# ZYNQ_PW.net
KiCad netlist of a schematic drawn in Altium Designer
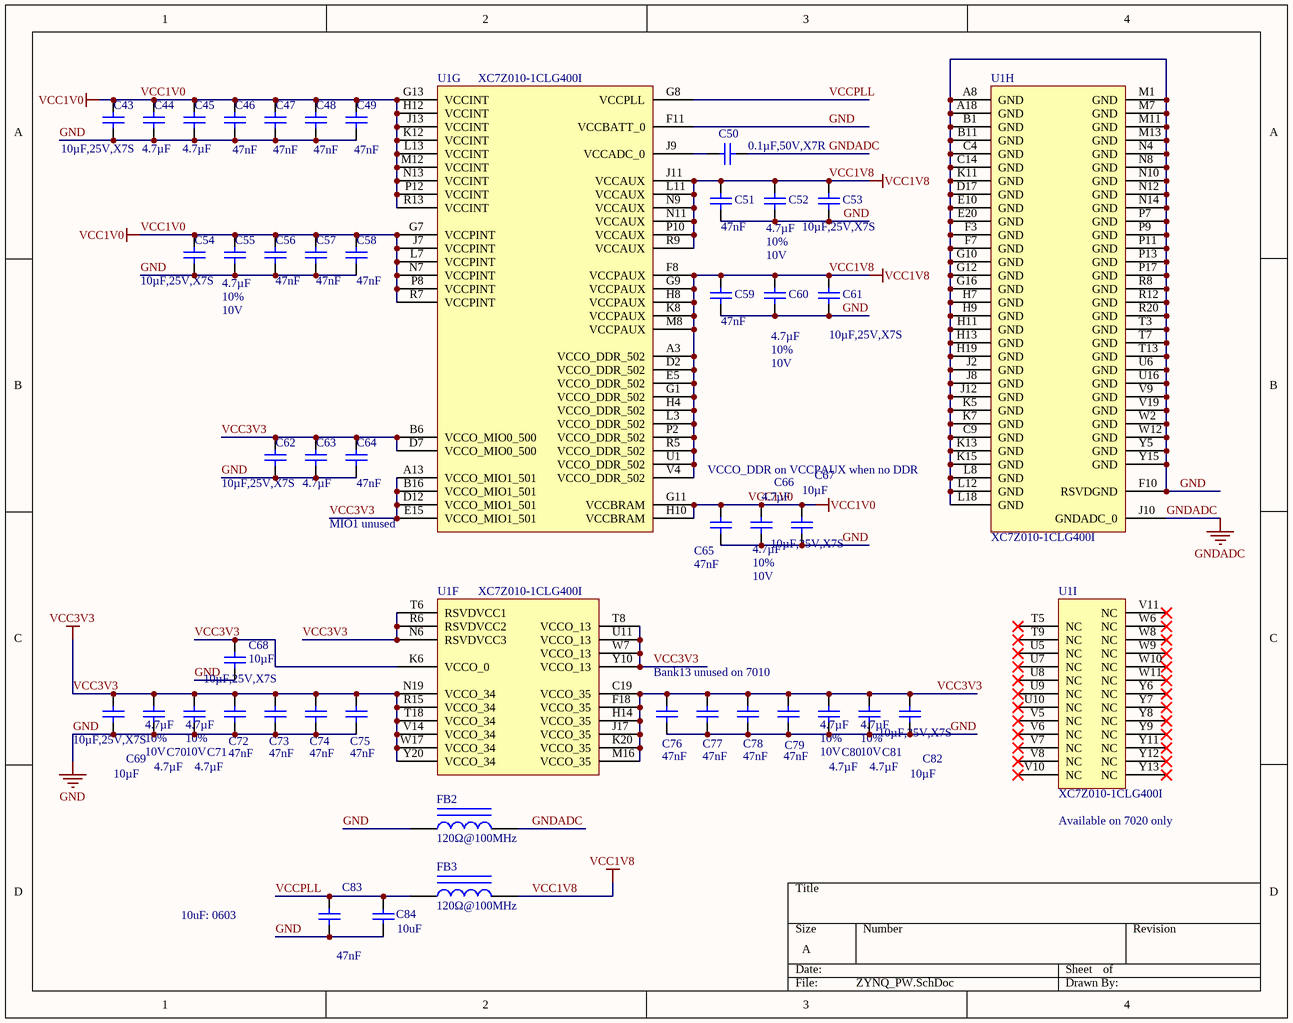
[diagram p0: ZYNQ_PW.SchDoc]

(export (version "E")
  (design (tool "Eeschema 10.0.6"))
  (components
    (comp (ref "C43")
      (value "10µF,25V,X7S")
      (footprint "CAP0805i")
      (description "0805, 10uF, 10%, 25V, X7S")
      (fields (field (name "PART NUMBER") "GRT21BC71E106KE13L") (field (name "VOLTAGE") "25V"))
      (libsource (lib "AmpherLib") (part "Cap_10uF_50V_X7S_0805"))
    )
    (comp (ref "C44")
      (value "4.7µF")
      (footprint "CAP0402i")
      (description "CAP CER 4.7UF 10V X5R 0402")
      (fields (field (name "PART NUMBER") "C1005X5R1A475K050BC") (field (name "TOLERANCE") "10%"))
      (libsource (lib "AmpherLib") (part "Cap_4.7uF_10V_10%_0402"))
    )
    (comp (ref "C45")
      (value "4.7µF")
      (footprint "CAP0402i")
      (description "CAP CER 4.7UF 10V X5R 0402")
      (fields
        (field (name "PART NUMBER") "C1005X5R1A475K050BC")
        (field (name "CAPACITANCE") "4.7µF")
        (field (name "TOLERANCE") "10%")
      )
      (libsource (lib "AmpherLib") (part "Cap_4.7uF_10V_10%_0402"))
    )
    (comp (ref "C46")
      (value "~")
      (footprint "CAP0201i")
      (description "0201, 47nF, 10%, 25V, X7R")
      (fields (field (name "CAPACITANCE") "47nF"))
      (libsource (lib "AmpherLib") (part "Cap_47nF_X7R_0201"))
    )
    (comp (ref "C47")
      (value "~")
      (footprint "CAP0201i")
      (description "0201, 47nF, 10%, 25V, X7R")
      (fields (field (name "CAPACITANCE") "47nF"))
      (libsource (lib "AmpherLib") (part "Cap_47nF_X7R_0201"))
    )
    (comp (ref "C48")
      (value "~")
      (footprint "CAP0201i")
      (description "0201, 47nF, 10%, 25V, X7R")
      (fields (field (name "CAPACITANCE") "47nF"))
      (libsource (lib "AmpherLib") (part "Cap_47nF_X7R_0201"))
    )
    (comp (ref "C49")
      (value "~")
      (footprint "CAP0201i")
      (description "0201, 47nF, 10%, 25V, X7R")
      (fields (field (name "CAPACITANCE") "47nF"))
      (libsource (lib "AmpherLib") (part "Cap_47nF_X7R_0201"))
    )
    (comp (ref "C50")
      (value "0.1µF,50V,X7R")
      (footprint "CAP0402i")
      (description "0402, 0.1uF, 10%,  50V, X7R")
      (fields (field (name "PART NUMBER") "C1005X7R1H104K050BE") (field (name "VOLTAGE") "50V"))
      (libsource (lib "AmpherLib") (part "Cap_0.1uF_50V_X7R_0402"))
    )
    (comp (ref "C51")
      (value "~")
      (footprint "CAP0201i")
      (description "0201, 47nF, 10%, 25V, X7R")
      (fields (field (name "CAPACITANCE") "47nF"))
      (libsource (lib "AmpherLib") (part "Cap_47nF_X7R_0201"))
    )
    (comp (ref "C52")
      (value "4.7µF")
      (footprint "CAP0402i")
      (description "CAP CER 4.7UF 10V X5R 0402")
      (fields
        (field (name "PART NUMBER") "C1005X5R1A475K050BC")
        (field (name "CAPACITANCE") "4.7µF")
        (field (name "TOLERANCE") "10%")
        (field (name "VOLTAGE RATING") "10V")
      )
      (libsource (lib "AmpherLib") (part "Cap_4.7uF_10V_10%_0402"))
    )
    (comp (ref "C53")
      (value "10µF,25V,X7S")
      (footprint "CAP0805i")
      (description "0805, 10uF, 10%, 25V, X7S")
      (fields (field (name "PART NUMBER") "GRT21BC71E106KE13L") (field (name "VOLTAGE") "25V"))
      (libsource (lib "AmpherLib") (part "Cap_10uF_50V_X7S_0805"))
    )
    (comp (ref "C54")
      (value "10µF,25V,X7S")
      (footprint "CAP0805i")
      (description "0805, 10uF, 10%, 25V, X7S")
      (fields (field (name "PART NUMBER") "GRT21BC71E106KE13L") (field (name "VOLTAGE") "25V"))
      (libsource (lib "AmpherLib") (part "Cap_10uF_50V_X7S_0805"))
    )
    (comp (ref "C55")
      (value "4.7µF")
      (footprint "CAP0402i")
      (description "CAP CER 4.7UF 10V X5R 0402")
      (fields
        (field (name "PART NUMBER") "C1005X5R1A475K050BC")
        (field (name "CAPACITANCE") "4.7µF")
        (field (name "TOLERANCE") "10%")
        (field (name "VOLTAGE RATING") "10V")
      )
      (libsource (lib "AmpherLib") (part "Cap_4.7uF_10V_10%_0402"))
    )
    (comp (ref "C56")
      (value "~")
      (footprint "CAP0201i")
      (description "0201, 47nF, 10%, 25V, X7R")
      (fields (field (name "CAPACITANCE") "47nF"))
      (libsource (lib "AmpherLib") (part "Cap_47nF_X7R_0201"))
    )
    (comp (ref "C57")
      (value "~")
      (footprint "CAP0201i")
      (description "0201, 47nF, 10%, 25V, X7R")
      (fields (field (name "CAPACITANCE") "47nF"))
      (libsource (lib "AmpherLib") (part "Cap_47nF_X7R_0201"))
    )
    (comp (ref "C58")
      (value "~")
      (footprint "CAP0201i")
      (description "0201, 47nF, 10%, 25V, X7R")
      (fields (field (name "CAPACITANCE") "47nF"))
      (libsource (lib "AmpherLib") (part "Cap_47nF_X7R_0201"))
    )
    (comp (ref "C59")
      (value "~")
      (footprint "CAP0201i")
      (description "0201, 47nF, 10%, 25V, X7R")
      (fields (field (name "CAPACITANCE") "47nF"))
      (libsource (lib "AmpherLib") (part "Cap_47nF_X7R_0201"))
    )
    (comp (ref "C60")
      (value "4.7µF")
      (footprint "CAP0402i")
      (description "CAP CER 4.7UF 10V X5R 0402")
      (fields
        (field (name "PART NUMBER") "C1005X5R1A475K050BC")
        (field (name "CAPACITANCE") "4.7µF")
        (field (name "TOLERANCE") "10%")
        (field (name "VOLTAGE RATING") "10V")
      )
      (libsource (lib "AmpherLib") (part "Cap_4.7uF_10V_10%_0402"))
    )
    (comp (ref "C61")
      (value "10µF,25V,X7S")
      (footprint "CAP0805i")
      (description "0805, 10uF, 10%, 25V, X7S")
      (fields (field (name "PART NUMBER") "GRT21BC71E106KE13L") (field (name "VOLTAGE") "25V"))
      (libsource (lib "AmpherLib") (part "Cap_10uF_50V_X7S_0805"))
    )
    (comp (ref "C62")
      (value "10µF,25V,X7S")
      (footprint "CAP0805i")
      (description "0805, 10uF, 10%, 25V, X7S")
      (fields (field (name "PART NUMBER") "GRT21BC71E106KE13L") (field (name "VOLTAGE") "25V"))
      (libsource (lib "AmpherLib") (part "Cap_10uF_50V_X7S_0805"))
    )
    (comp (ref "C63")
      (value "4.7µF")
      (footprint "CAP0402i")
      (description "CAP CER 4.7UF 10V X5R 0402")
      (fields (field (name "PART NUMBER") "C1005X5R1A475K050BC") (field (name "TOLERANCE") "10%"))
      (libsource (lib "AmpherLib") (part "Cap_4.7uF_10V_10%_0402"))
    )
    (comp (ref "C64")
      (value "~")
      (footprint "CAP0201i")
      (description "0201, 47nF, 10%, 25V, X7R")
      (fields (field (name "CAPACITANCE") "47nF"))
      (libsource (lib "AmpherLib") (part "Cap_47nF_X7R_0201"))
    )
    (comp (ref "C65")
      (value "~")
      (footprint "CAP0201i")
      (description "0201, 47nF, 10%, 25V, X7R")
      (fields (field (name "CAPACITANCE") "47nF"))
      (libsource (lib "AmpherLib") (part "Cap_47nF_X7R_0201"))
    )
    (comp (ref "C66")
      (value "4.7µF")
      (footprint "CAP0402i")
      (description "CAP CER 4.7UF 10V X5R 0402")
      (fields
        (field (name "PART NUMBER") "C1005X5R1A475K050BC")
        (field (name "CAPACITANCE") "4.7µF")
        (field (name "TOLERANCE") "10%")
        (field (name "VOLTAGE RATING") "10V")
      )
      (libsource (lib "AmpherLib") (part "Cap_4.7uF_10V_10%_0402"))
    )
    (comp (ref "C67")
      (value "10µF")
      (footprint "CAP0805i")
      (description "0805, 10uF, 10%, 25V, X7S")
      (fields
        (field (name "PART NUMBER") "GRT21BC71E106KE13L")
        (field (name "VOLTAGE") "25V")
        (field (name "ALTIUM_VALUE") "10µF,25V,X7S")
      )
      (libsource (lib "AmpherLib") (part "Cap_10uF_50V_X7S_0805"))
    )
    (comp (ref "C68")
      (value "10µF")
      (footprint "CAP0805i")
      (description "0805, 10uF, 10%, 25V, X7S")
      (fields
        (field (name "PART NUMBER") "GRT21BC71E106KE13L")
        (field (name "VOLTAGE") "25V")
        (field (name "ALTIUM_VALUE") "10µF,25V,X7S")
      )
      (libsource (lib "AmpherLib") (part "Cap_10uF_50V_X7S_0805"))
    )
    (comp (ref "C69")
      (value "10µF")
      (footprint "CAP0805i")
      (description "0805, 10uF, 10%, 25V, X7S")
      (fields
        (field (name "PART NUMBER") "GRT21BC71E106KE13L")
        (field (name "VOLTAGE") "25V")
        (field (name "ALTIUM_VALUE") "10µF,25V,X7S")
      )
      (libsource (lib "AmpherLib") (part "Cap_10uF_50V_X7S_0805"))
    )
    (comp (ref "C70")
      (value "4.7µF")
      (footprint "CAP0402i")
      (description "CAP CER 4.7UF 10V X5R 0402")
      (fields
        (field (name "PART NUMBER") "C1005X5R1A475K050BC")
        (field (name "CAPACITANCE") "4.7µF")
        (field (name "TOLERANCE") "10%")
        (field (name "VOLTAGE RATING") "10V")
      )
      (libsource (lib "AmpherLib") (part "Cap_4.7uF_10V_10%_0402"))
    )
    (comp (ref "C71")
      (value "4.7µF")
      (footprint "CAP0402i")
      (description "CAP CER 4.7UF 10V X5R 0402")
      (fields
        (field (name "PART NUMBER") "C1005X5R1A475K050BC")
        (field (name "CAPACITANCE") "4.7µF")
        (field (name "TOLERANCE") "10%")
        (field (name "VOLTAGE RATING") "10V")
      )
      (libsource (lib "AmpherLib") (part "Cap_4.7uF_10V_10%_0402"))
    )
    (comp (ref "C72")
      (value "~")
      (footprint "CAP0201i")
      (description "0201, 47nF, 10%, 25V, X7R")
      (fields (field (name "CAPACITANCE") "47nF"))
      (libsource (lib "AmpherLib") (part "Cap_47nF_X7R_0201"))
    )
    (comp (ref "C73")
      (value "~")
      (footprint "CAP0201i")
      (description "0201, 47nF, 10%, 25V, X7R")
      (fields (field (name "CAPACITANCE") "47nF"))
      (libsource (lib "AmpherLib") (part "Cap_47nF_X7R_0201"))
    )
    (comp (ref "C74")
      (value "~")
      (footprint "CAP0201i")
      (description "0201, 47nF, 10%, 25V, X7R")
      (fields (field (name "CAPACITANCE") "47nF"))
      (libsource (lib "AmpherLib") (part "Cap_47nF_X7R_0201"))
    )
    (comp (ref "C75")
      (value "~")
      (footprint "CAP0201i")
      (description "0201, 47nF, 10%, 25V, X7R")
      (fields (field (name "CAPACITANCE") "47nF"))
      (libsource (lib "AmpherLib") (part "Cap_47nF_X7R_0201"))
    )
    (comp (ref "C76")
      (value "~")
      (footprint "CAP0201i")
      (description "0201, 47nF, 10%, 25V, X7R")
      (fields (field (name "CAPACITANCE") "47nF"))
      (libsource (lib "AmpherLib") (part "Cap_47nF_X7R_0201"))
    )
    (comp (ref "C77")
      (value "~")
      (footprint "CAP0201i")
      (description "0201, 47nF, 10%, 25V, X7R")
      (fields (field (name "CAPACITANCE") "47nF"))
      (libsource (lib "AmpherLib") (part "Cap_47nF_X7R_0201"))
    )
    (comp (ref "C78")
      (value "~")
      (footprint "CAP0201i")
      (description "0201, 47nF, 10%, 25V, X7R")
      (fields (field (name "CAPACITANCE") "47nF"))
      (libsource (lib "AmpherLib") (part "Cap_47nF_X7R_0201"))
    )
    (comp (ref "C79")
      (value "~")
      (footprint "CAP0201i")
      (description "0201, 47nF, 10%, 25V, X7R")
      (fields (field (name "CAPACITANCE") "47nF"))
      (libsource (lib "AmpherLib") (part "Cap_47nF_X7R_0201"))
    )
    (comp (ref "C80")
      (value "4.7µF")
      (footprint "CAP0402i")
      (description "CAP CER 4.7UF 10V X5R 0402")
      (fields
        (field (name "PART NUMBER") "C1005X5R1A475K050BC")
        (field (name "CAPACITANCE") "4.7µF")
        (field (name "TOLERANCE") "10%")
        (field (name "VOLTAGE RATING") "10V")
      )
      (libsource (lib "AmpherLib") (part "Cap_4.7uF_10V_10%_0402"))
    )
    (comp (ref "C81")
      (value "4.7µF")
      (footprint "CAP0402i")
      (description "CAP CER 4.7UF 10V X5R 0402")
      (fields
        (field (name "PART NUMBER") "C1005X5R1A475K050BC")
        (field (name "CAPACITANCE") "4.7µF")
        (field (name "TOLERANCE") "10%")
        (field (name "VOLTAGE RATING") "10V")
      )
      (libsource (lib "AmpherLib") (part "Cap_4.7uF_10V_10%_0402"))
    )
    (comp (ref "C82")
      (value "10µF")
      (footprint "CAP0805i")
      (description "0805, 10uF, 10%, 25V, X7S")
      (fields
        (field (name "PART NUMBER") "GRT21BC71E106KE13L")
        (field (name "VOLTAGE") "25V")
        (field (name "ALTIUM_VALUE") "10µF,25V,X7S")
      )
      (libsource (lib "AmpherLib") (part "Cap_10uF_50V_X7S_0805"))
    )
    (comp (ref "C83")
      (value "~")
      (footprint "CAP0201i")
      (description "0201, 47nF, 10%, 25V, X7R")
      (fields (field (name "CAPACITANCE") "47nF"))
      (libsource (lib "AmpherLib") (part "Cap_47nF_X7R_0201"))
    )
    (comp (ref "C84")
      (value "10uF")
      (footprint "0603_C")
      (description "贴片电容")
      (libsource (lib "Cap") (part "0603 10uF (106) 10% 10V"))
    )
    (comp (ref "FB2")
      (value "120Ω@100MHz")
      (footprint "0805_L")
      (description "贴片磁珠")
      (libsource (lib "IUD") (part "0805 600Ω 25% 100MHz"))
    )
    (comp (ref "FB3")
      (value "120Ω@100MHz")
      (footprint "0805_L")
      (description "贴片磁珠")
      (libsource (lib "IUD") (part "0805 600Ω 25% 100MHz"))
    )
    (comp (ref "U1")
      (value "XC7Z010-1CLG400I")
      (footprint "CLG400")
      (fields (field (name "GENERIC PART NUMBER") "XC7Z010") (field (name "MANUFACTURER") "Xilinx"))
      (libsource (lib "CCZynq") (part "XC7Z010-1CLG400I"))
    )
  )
  (nets
    (net (code "1") (name "/VCCPLL") (class "Default")
      (node (ref "C83") (pin "2") (pinfunction "2_2") (pintype "passive"))
      (node (ref "C84") (pin "2") (pinfunction "2_2") (pintype "passive"))
      (node (ref "FB3") (pin "1") (pinfunction "1_1") (pintype "passive"))
      (node (ref "U1") (pin "G8") (pinfunction "VCCPLL_G8") (pintype "power_in"))
    )
    (net (code "2") (name "GND") (class "Default")
      (node (ref "C43") (pin "2") (pinfunction "2_2") (pintype "passive"))
      (node (ref "C44") (pin "2") (pinfunction "2_2") (pintype "passive"))
      (node (ref "C45") (pin "2") (pinfunction "2_2") (pintype "passive"))
      (node (ref "C46") (pin "2") (pinfunction "2_2") (pintype "passive"))
      (node (ref "C47") (pin "2") (pinfunction "2_2") (pintype "passive"))
      (node (ref "C48") (pin "2") (pinfunction "2_2") (pintype "passive"))
      (node (ref "C49") (pin "2") (pinfunction "2_2") (pintype "passive"))
      (node (ref "C51") (pin "1") (pinfunction "1_1") (pintype "passive"))
      (node (ref "C52") (pin "1") (pinfunction "1_1") (pintype "passive"))
      (node (ref "C53") (pin "1") (pinfunction "1_1") (pintype "passive"))
      (node (ref "C54") (pin "2") (pinfunction "2_2") (pintype "passive"))
      (node (ref "C55") (pin "2") (pinfunction "2_2") (pintype "passive"))
      (node (ref "C56") (pin "2") (pinfunction "2_2") (pintype "passive"))
      (node (ref "C57") (pin "2") (pinfunction "2_2") (pintype "passive"))
      (node (ref "C58") (pin "2") (pinfunction "2_2") (pintype "passive"))
      (node (ref "C59") (pin "1") (pinfunction "1_1") (pintype "passive"))
      (node (ref "C60") (pin "1") (pinfunction "1_1") (pintype "passive"))
      (node (ref "C61") (pin "1") (pinfunction "1_1") (pintype "passive"))
      (node (ref "C62") (pin "2") (pinfunction "2_2") (pintype "passive"))
      (node (ref "C63") (pin "2") (pinfunction "2_2") (pintype "passive"))
      (node (ref "C64") (pin "2") (pinfunction "2_2") (pintype "passive"))
      (node (ref "C65") (pin "1") (pinfunction "1_1") (pintype "passive"))
      (node (ref "C66") (pin "1") (pinfunction "1_1") (pintype "passive"))
      (node (ref "C67") (pin "1") (pinfunction "1_1") (pintype "passive"))
      (node (ref "C68") (pin "1") (pinfunction "1_1") (pintype "passive"))
      (node (ref "C69") (pin "2") (pinfunction "2_2") (pintype "passive"))
      (node (ref "C70") (pin "2") (pinfunction "2_2") (pintype "passive"))
      (node (ref "C71") (pin "2") (pinfunction "2_2") (pintype "passive"))
      (node (ref "C72") (pin "2") (pinfunction "2_2") (pintype "passive"))
      (node (ref "C73") (pin "2") (pinfunction "2_2") (pintype "passive"))
      (node (ref "C74") (pin "2") (pinfunction "2_2") (pintype "passive"))
      (node (ref "C75") (pin "2") (pinfunction "2_2") (pintype "passive"))
      (node (ref "C76") (pin "2") (pinfunction "2_2") (pintype "passive"))
      (node (ref "C77") (pin "2") (pinfunction "2_2") (pintype "passive"))
      (node (ref "C78") (pin "2") (pinfunction "2_2") (pintype "passive"))
      (node (ref "C79") (pin "2") (pinfunction "2_2") (pintype "passive"))
      (node (ref "C80") (pin "2") (pinfunction "2_2") (pintype "passive"))
      (node (ref "C81") (pin "2") (pinfunction "2_2") (pintype "passive"))
      (node (ref "C82") (pin "2") (pinfunction "2_2") (pintype "passive"))
      (node (ref "C83") (pin "1") (pinfunction "1_1") (pintype "passive"))
      (node (ref "C84") (pin "1") (pinfunction "1_1") (pintype "passive"))
      (node (ref "FB2") (pin "1") (pinfunction "1_1") (pintype "passive"))
      (node (ref "U1") (pin "A18") (pinfunction "GND_A18") (pintype "power_in"))
      (node (ref "U1") (pin "A8") (pinfunction "GND_A8") (pintype "power_in"))
      (node (ref "U1") (pin "B1") (pinfunction "GND_B1") (pintype "power_in"))
      (node (ref "U1") (pin "B11") (pinfunction "GND_B11") (pintype "power_in"))
      (node (ref "U1") (pin "C14") (pinfunction "GND_C14") (pintype "power_in"))
      (node (ref "U1") (pin "C4") (pinfunction "GND_C4") (pintype "power_in"))
      (node (ref "U1") (pin "C9") (pinfunction "GND_C9") (pintype "power_in"))
      (node (ref "U1") (pin "D17") (pinfunction "GND_D17") (pintype "power_in"))
      (node (ref "U1") (pin "E10") (pinfunction "GND_E10") (pintype "power_in"))
      (node (ref "U1") (pin "E20") (pinfunction "GND_E20") (pintype "power_in"))
      (node (ref "U1") (pin "F10") (pinfunction "RSVDGND_F10") (pintype "power_in"))
      (node (ref "U1") (pin "F11") (pinfunction "VCCBATT_0_F11") (pintype "power_in"))
      (node (ref "U1") (pin "F3") (pinfunction "GND_F3") (pintype "power_in"))
      (node (ref "U1") (pin "F7") (pinfunction "GND_F7") (pintype "power_in"))
      (node (ref "U1") (pin "G10") (pinfunction "GND_G10") (pintype "power_in"))
      (node (ref "U1") (pin "G12") (pinfunction "GND_G12") (pintype "power_in"))
      (node (ref "U1") (pin "G16") (pinfunction "GND_G16") (pintype "power_in"))
      (node (ref "U1") (pin "H11") (pinfunction "GND_H11") (pintype "power_in"))
      (node (ref "U1") (pin "H13") (pinfunction "GND_H13") (pintype "power_in"))
      (node (ref "U1") (pin "H19") (pinfunction "GND_H19") (pintype "power_in"))
      (node (ref "U1") (pin "H7") (pinfunction "GND_H7") (pintype "power_in"))
      (node (ref "U1") (pin "H9") (pinfunction "GND_H9") (pintype "power_in"))
      (node (ref "U1") (pin "J12") (pinfunction "GND_J12") (pintype "power_in"))
      (node (ref "U1") (pin "J2") (pinfunction "GND_J2") (pintype "power_in"))
      (node (ref "U1") (pin "J8") (pinfunction "GND_J8") (pintype "power_in"))
      (node (ref "U1") (pin "K11") (pinfunction "GND_K11") (pintype "power_in"))
      (node (ref "U1") (pin "K13") (pinfunction "GND_K13") (pintype "power_in"))
      (node (ref "U1") (pin "K15") (pinfunction "GND_K15") (pintype "power_in"))
      (node (ref "U1") (pin "K5") (pinfunction "GND_K5") (pintype "power_in"))
      (node (ref "U1") (pin "K7") (pinfunction "GND_K7") (pintype "power_in"))
      (node (ref "U1") (pin "L12") (pinfunction "GND_L12") (pintype "power_in"))
      (node (ref "U1") (pin "L18") (pinfunction "GND_L18") (pintype "power_in"))
      (node (ref "U1") (pin "L8") (pinfunction "GND_L8") (pintype "power_in"))
      (node (ref "U1") (pin "M1") (pinfunction "GND_M1") (pintype "power_in"))
      (node (ref "U1") (pin "M11") (pinfunction "GND_M11") (pintype "power_in"))
      (node (ref "U1") (pin "M13") (pinfunction "GND_M13") (pintype "power_in"))
      (node (ref "U1") (pin "M7") (pinfunction "GND_M7") (pintype "power_in"))
      (node (ref "U1") (pin "N10") (pinfunction "GND_N10") (pintype "power_in"))
      (node (ref "U1") (pin "N12") (pinfunction "GND_N12") (pintype "power_in"))
      (node (ref "U1") (pin "N14") (pinfunction "GND_N14") (pintype "power_in"))
      (node (ref "U1") (pin "N4") (pinfunction "GND_N4") (pintype "power_in"))
      (node (ref "U1") (pin "N8") (pinfunction "GND_N8") (pintype "power_in"))
      (node (ref "U1") (pin "P11") (pinfunction "GND_P11") (pintype "power_in"))
      (node (ref "U1") (pin "P13") (pinfunction "GND_P13") (pintype "power_in"))
      (node (ref "U1") (pin "P17") (pinfunction "GND_P17") (pintype "power_in"))
      (node (ref "U1") (pin "P7") (pinfunction "GND_P7") (pintype "power_in"))
      (node (ref "U1") (pin "P9") (pinfunction "GND_P9") (pintype "power_in"))
      (node (ref "U1") (pin "R12") (pinfunction "GND_R12") (pintype "power_in"))
      (node (ref "U1") (pin "R20") (pinfunction "GND_R20") (pintype "power_in"))
      (node (ref "U1") (pin "R8") (pinfunction "GND_R8") (pintype "power_in"))
      (node (ref "U1") (pin "T13") (pinfunction "GND_T13") (pintype "power_in"))
      (node (ref "U1") (pin "T3") (pinfunction "GND_T3") (pintype "power_in"))
      (node (ref "U1") (pin "T7") (pinfunction "GND_T7") (pintype "power_in"))
      (node (ref "U1") (pin "U16") (pinfunction "GND_U16") (pintype "power_in"))
      (node (ref "U1") (pin "U6") (pinfunction "GND_U6") (pintype "power_in"))
      (node (ref "U1") (pin "V19") (pinfunction "GND_V19") (pintype "power_in"))
      (node (ref "U1") (pin "V9") (pinfunction "GND_V9") (pintype "power_in"))
      (node (ref "U1") (pin "W12") (pinfunction "GND_W12") (pintype "power_in"))
      (node (ref "U1") (pin "W2") (pinfunction "GND_W2") (pintype "power_in"))
      (node (ref "U1") (pin "Y15") (pinfunction "GND_Y15") (pintype "power_in"))
      (node (ref "U1") (pin "Y5") (pinfunction "GND_Y5") (pintype "power_in"))
    )
    (net (code "3") (name "GNDADC") (class "Default")
      (node (ref "C50") (pin "2") (pinfunction "2_2") (pintype "passive"))
      (node (ref "FB2") (pin "2") (pinfunction "2_2") (pintype "passive"))
      (node (ref "U1") (pin "J10") (pinfunction "GNDADC_0_J10") (pintype "power_in"))
    )
    (net (code "4") (name "Net-(U1G-VCCADC_0)") (class "Default")
      (node (ref "C50") (pin "1") (pinfunction "1_1") (pintype "passive"))
      (node (ref "U1") (pin "J9") (pinfunction "VCCADC_0_J9") (pintype "power_in"))
    )
    (net (code "5") (name "VCC1V0") (class "Default")
      (node (ref "C43") (pin "1") (pinfunction "1_1") (pintype "passive"))
      (node (ref "C44") (pin "1") (pinfunction "1_1") (pintype "passive"))
      (node (ref "C45") (pin "1") (pinfunction "1_1") (pintype "passive"))
      (node (ref "C46") (pin "1") (pinfunction "1_1") (pintype "passive"))
      (node (ref "C47") (pin "1") (pinfunction "1_1") (pintype "passive"))
      (node (ref "C48") (pin "1") (pinfunction "1_1") (pintype "passive"))
      (node (ref "C49") (pin "1") (pinfunction "1_1") (pintype "passive"))
      (node (ref "C54") (pin "1") (pinfunction "1_1") (pintype "passive"))
      (node (ref "C55") (pin "1") (pinfunction "1_1") (pintype "passive"))
      (node (ref "C56") (pin "1") (pinfunction "1_1") (pintype "passive"))
      (node (ref "C57") (pin "1") (pinfunction "1_1") (pintype "passive"))
      (node (ref "C58") (pin "1") (pinfunction "1_1") (pintype "passive"))
      (node (ref "C65") (pin "2") (pinfunction "2_2") (pintype "passive"))
      (node (ref "C66") (pin "2") (pinfunction "2_2") (pintype "passive"))
      (node (ref "C67") (pin "2") (pinfunction "2_2") (pintype "passive"))
      (node (ref "U1") (pin "G11") (pinfunction "VCCBRAM_G11") (pintype "power_in"))
      (node (ref "U1") (pin "G13") (pinfunction "VCCINT_G13") (pintype "power_in"))
      (node (ref "U1") (pin "G7") (pinfunction "VCCPINT_G7") (pintype "power_in"))
      (node (ref "U1") (pin "H10") (pinfunction "VCCBRAM_H10") (pintype "power_in"))
      (node (ref "U1") (pin "H12") (pinfunction "VCCINT_H12") (pintype "power_in"))
      (node (ref "U1") (pin "J13") (pinfunction "VCCINT_J13") (pintype "power_in"))
      (node (ref "U1") (pin "J7") (pinfunction "VCCPINT_J7") (pintype "power_in"))
      (node (ref "U1") (pin "K12") (pinfunction "VCCINT_K12") (pintype "power_in"))
      (node (ref "U1") (pin "L13") (pinfunction "VCCINT_L13") (pintype "power_in"))
      (node (ref "U1") (pin "L7") (pinfunction "VCCPINT_L7") (pintype "power_in"))
      (node (ref "U1") (pin "M12") (pinfunction "VCCINT_M12") (pintype "power_in"))
      (node (ref "U1") (pin "N13") (pinfunction "VCCINT_N13") (pintype "power_in"))
      (node (ref "U1") (pin "N7") (pinfunction "VCCPINT_N7") (pintype "power_in"))
      (node (ref "U1") (pin "P12") (pinfunction "VCCINT_P12") (pintype "power_in"))
      (node (ref "U1") (pin "P8") (pinfunction "VCCPINT_P8") (pintype "power_in"))
      (node (ref "U1") (pin "R13") (pinfunction "VCCINT_R13") (pintype "power_in"))
      (node (ref "U1") (pin "R7") (pinfunction "VCCPINT_R7") (pintype "power_in"))
    )
    (net (code "6") (name "VCC1V8") (class "Default")
      (node (ref "C51") (pin "2") (pinfunction "2_2") (pintype "passive"))
      (node (ref "C52") (pin "2") (pinfunction "2_2") (pintype "passive"))
      (node (ref "C53") (pin "2") (pinfunction "2_2") (pintype "passive"))
      (node (ref "C59") (pin "2") (pinfunction "2_2") (pintype "passive"))
      (node (ref "C60") (pin "2") (pinfunction "2_2") (pintype "passive"))
      (node (ref "C61") (pin "2") (pinfunction "2_2") (pintype "passive"))
      (node (ref "FB3") (pin "2") (pinfunction "2_2") (pintype "passive"))
      (node (ref "U1") (pin "A3") (pinfunction "VCCO_DDR_502_A3") (pintype "power_in"))
      (node (ref "U1") (pin "D2") (pinfunction "VCCO_DDR_502_D2") (pintype "power_in"))
      (node (ref "U1") (pin "E5") (pinfunction "VCCO_DDR_502_E5") (pintype "power_in"))
      (node (ref "U1") (pin "F8") (pinfunction "VCCPAUX_F8") (pintype "power_in"))
      (node (ref "U1") (pin "G1") (pinfunction "VCCO_DDR_502_G1") (pintype "power_in"))
      (node (ref "U1") (pin "G9") (pinfunction "VCCPAUX_G9") (pintype "power_in"))
      (node (ref "U1") (pin "H4") (pinfunction "VCCO_DDR_502_H4") (pintype "power_in"))
      (node (ref "U1") (pin "H8") (pinfunction "VCCPAUX_H8") (pintype "power_in"))
      (node (ref "U1") (pin "J11") (pinfunction "VCCAUX_J11") (pintype "power_in"))
      (node (ref "U1") (pin "K8") (pinfunction "VCCPAUX_K8") (pintype "power_in"))
      (node (ref "U1") (pin "L11") (pinfunction "VCCAUX_L11") (pintype "power_in"))
      (node (ref "U1") (pin "L3") (pinfunction "VCCO_DDR_502_L3") (pintype "power_in"))
      (node (ref "U1") (pin "M8") (pinfunction "VCCPAUX_M8") (pintype "power_in"))
      (node (ref "U1") (pin "N11") (pinfunction "VCCAUX_N11") (pintype "power_in"))
      (node (ref "U1") (pin "N9") (pinfunction "VCCAUX_N9") (pintype "power_in"))
      (node (ref "U1") (pin "P10") (pinfunction "VCCAUX_P10") (pintype "power_in"))
      (node (ref "U1") (pin "P2") (pinfunction "VCCO_DDR_502_P2") (pintype "power_in"))
      (node (ref "U1") (pin "R5") (pinfunction "VCCO_DDR_502_R5") (pintype "power_in"))
      (node (ref "U1") (pin "R9") (pinfunction "VCCAUX_R9") (pintype "power_in"))
      (node (ref "U1") (pin "U1") (pinfunction "VCCO_DDR_502_U1") (pintype "power_in"))
      (node (ref "U1") (pin "V4") (pinfunction "VCCO_DDR_502_V4") (pintype "power_in"))
    )
    (net (code "7") (name "VCC3V3") (class "Default")
      (node (ref "C62") (pin "1") (pinfunction "1_1") (pintype "passive"))
      (node (ref "C63") (pin "1") (pinfunction "1_1") (pintype "passive"))
      (node (ref "C64") (pin "1") (pinfunction "1_1") (pintype "passive"))
      (node (ref "C68") (pin "2") (pinfunction "2_2") (pintype "passive"))
      (node (ref "C69") (pin "1") (pinfunction "1_1") (pintype "passive"))
      (node (ref "C70") (pin "1") (pinfunction "1_1") (pintype "passive"))
      (node (ref "C71") (pin "1") (pinfunction "1_1") (pintype "passive"))
      (node (ref "C72") (pin "1") (pinfunction "1_1") (pintype "passive"))
      (node (ref "C73") (pin "1") (pinfunction "1_1") (pintype "passive"))
      (node (ref "C74") (pin "1") (pinfunction "1_1") (pintype "passive"))
      (node (ref "C75") (pin "1") (pinfunction "1_1") (pintype "passive"))
      (node (ref "C76") (pin "1") (pinfunction "1_1") (pintype "passive"))
      (node (ref "C77") (pin "1") (pinfunction "1_1") (pintype "passive"))
      (node (ref "C78") (pin "1") (pinfunction "1_1") (pintype "passive"))
      (node (ref "C79") (pin "1") (pinfunction "1_1") (pintype "passive"))
      (node (ref "C80") (pin "1") (pinfunction "1_1") (pintype "passive"))
      (node (ref "C81") (pin "1") (pinfunction "1_1") (pintype "passive"))
      (node (ref "C82") (pin "1") (pinfunction "1_1") (pintype "passive"))
      (node (ref "U1") (pin "A13") (pinfunction "VCCO_MIO1_501_A13") (pintype "power_in"))
      (node (ref "U1") (pin "B16") (pinfunction "VCCO_MIO1_501_B16") (pintype "power_in"))
      (node (ref "U1") (pin "B6") (pinfunction "VCCO_MIO0_500_B6") (pintype "power_in"))
      (node (ref "U1") (pin "C19") (pinfunction "VCCO_35_C19") (pintype "power_in"))
      (node (ref "U1") (pin "D12") (pinfunction "VCCO_MIO1_501_D12") (pintype "power_in"))
      (node (ref "U1") (pin "D7") (pinfunction "VCCO_MIO0_500_D7") (pintype "power_in"))
      (node (ref "U1") (pin "E15") (pinfunction "VCCO_MIO1_501_E15") (pintype "power_in"))
      (node (ref "U1") (pin "F18") (pinfunction "VCCO_35_F18") (pintype "power_in"))
      (node (ref "U1") (pin "H14") (pinfunction "VCCO_35_H14") (pintype "power_in"))
      (node (ref "U1") (pin "J17") (pinfunction "VCCO_35_J17") (pintype "power_in"))
      (node (ref "U1") (pin "K20") (pinfunction "VCCO_35_K20") (pintype "power_in"))
      (node (ref "U1") (pin "K6") (pinfunction "VCCO_0_K6") (pintype "power_in"))
      (node (ref "U1") (pin "M16") (pinfunction "VCCO_35_M16") (pintype "power_in"))
      (node (ref "U1") (pin "N19") (pinfunction "VCCO_34_N19") (pintype "power_in"))
      (node (ref "U1") (pin "N6") (pinfunction "RSVDVCC3_N6") (pintype "power_in"))
      (node (ref "U1") (pin "R15") (pinfunction "VCCO_34_R15") (pintype "power_in"))
      (node (ref "U1") (pin "R6") (pinfunction "RSVDVCC2_R6") (pintype "power_in"))
      (node (ref "U1") (pin "T18") (pinfunction "VCCO_34_T18") (pintype "power_in"))
      (node (ref "U1") (pin "T6") (pinfunction "RSVDVCC1_T6") (pintype "power_in"))
      (node (ref "U1") (pin "T8") (pinfunction "VCCO_13_T8") (pintype "power_in"))
      (node (ref "U1") (pin "U11") (pinfunction "VCCO_13_U11") (pintype "power_in"))
      (node (ref "U1") (pin "V14") (pinfunction "VCCO_34_V14") (pintype "power_in"))
      (node (ref "U1") (pin "W17") (pinfunction "VCCO_34_W17") (pintype "power_in"))
      (node (ref "U1") (pin "W7") (pinfunction "VCCO_13_W7") (pintype "power_in"))
      (node (ref "U1") (pin "Y10") (pinfunction "VCCO_13_Y10") (pintype "power_in"))
      (node (ref "U1") (pin "Y20") (pinfunction "VCCO_34_Y20") (pintype "power_in"))
    )
    (net (code "8") (name "unconnected-(U1I-NC-PadT5)") (class "Default")
      (node (ref "U1") (pin "T5") (pinfunction "NC_T5") (pintype "passive+no_connect"))
    )
    (net (code "9") (name "unconnected-(U1I-NC-PadT9)") (class "Default")
      (node (ref "U1") (pin "T9") (pinfunction "NC_T9") (pintype "passive+no_connect"))
    )
    (net (code "10") (name "unconnected-(U1I-NC-PadU5)") (class "Default")
      (node (ref "U1") (pin "U5") (pinfunction "NC_U5") (pintype "passive+no_connect"))
    )
    (net (code "11") (name "unconnected-(U1I-NC-PadU7)") (class "Default")
      (node (ref "U1") (pin "U7") (pinfunction "NC_U7") (pintype "passive+no_connect"))
    )
    (net (code "12") (name "unconnected-(U1I-NC-PadU8)") (class "Default")
      (node (ref "U1") (pin "U8") (pinfunction "NC_U8") (pintype "passive+no_connect"))
    )
    (net (code "13") (name "unconnected-(U1I-NC-PadU9)") (class "Default")
      (node (ref "U1") (pin "U9") (pinfunction "NC_U9") (pintype "passive+no_connect"))
    )
    (net (code "14") (name "unconnected-(U1I-NC-PadU10)") (class "Default")
      (node (ref "U1") (pin "U10") (pinfunction "NC_U10") (pintype "passive+no_connect"))
    )
    (net (code "15") (name "unconnected-(U1I-NC-PadV5)") (class "Default")
      (node (ref "U1") (pin "V5") (pinfunction "NC_V5") (pintype "passive+no_connect"))
    )
    (net (code "16") (name "unconnected-(U1I-NC-PadV6)") (class "Default")
      (node (ref "U1") (pin "V6") (pinfunction "NC_V6") (pintype "passive+no_connect"))
    )
    (net (code "17") (name "unconnected-(U1I-NC-PadV7)") (class "Default")
      (node (ref "U1") (pin "V7") (pinfunction "NC_V7") (pintype "passive+no_connect"))
    )
    (net (code "18") (name "unconnected-(U1I-NC-PadV8)") (class "Default")
      (node (ref "U1") (pin "V8") (pinfunction "NC_V8") (pintype "passive+no_connect"))
    )
    (net (code "19") (name "unconnected-(U1I-NC-PadV10)") (class "Default")
      (node (ref "U1") (pin "V10") (pinfunction "NC_V10") (pintype "passive+no_connect"))
    )
    (net (code "20") (name "unconnected-(U1I-NC-PadV11)") (class "Default")
      (node (ref "U1") (pin "V11") (pinfunction "NC_V11") (pintype "passive+no_connect"))
    )
    (net (code "21") (name "unconnected-(U1I-NC-PadW6)") (class "Default")
      (node (ref "U1") (pin "W6") (pinfunction "NC_W6") (pintype "passive+no_connect"))
    )
    (net (code "22") (name "unconnected-(U1I-NC-PadW8)") (class "Default")
      (node (ref "U1") (pin "W8") (pinfunction "NC_W8") (pintype "passive+no_connect"))
    )
    (net (code "23") (name "unconnected-(U1I-NC-PadW9)") (class "Default")
      (node (ref "U1") (pin "W9") (pinfunction "NC_W9") (pintype "passive+no_connect"))
    )
    (net (code "24") (name "unconnected-(U1I-NC-PadW10)") (class "Default")
      (node (ref "U1") (pin "W10") (pinfunction "NC_W10") (pintype "passive+no_connect"))
    )
    (net (code "25") (name "unconnected-(U1I-NC-PadW11)") (class "Default")
      (node (ref "U1") (pin "W11") (pinfunction "NC_W11") (pintype "passive+no_connect"))
    )
    (net (code "26") (name "unconnected-(U1I-NC-PadY6)") (class "Default")
      (node (ref "U1") (pin "Y6") (pinfunction "NC_Y6") (pintype "passive+no_connect"))
    )
    (net (code "27") (name "unconnected-(U1I-NC-PadY7)") (class "Default")
      (node (ref "U1") (pin "Y7") (pinfunction "NC_Y7") (pintype "passive+no_connect"))
    )
    (net (code "28") (name "unconnected-(U1I-NC-PadY8)") (class "Default")
      (node (ref "U1") (pin "Y8") (pinfunction "NC_Y8") (pintype "passive+no_connect"))
    )
    (net (code "29") (name "unconnected-(U1I-NC-PadY9)") (class "Default")
      (node (ref "U1") (pin "Y9") (pinfunction "NC_Y9") (pintype "passive+no_connect"))
    )
    (net (code "30") (name "unconnected-(U1I-NC-PadY11)") (class "Default")
      (node (ref "U1") (pin "Y11") (pinfunction "NC_Y11") (pintype "passive+no_connect"))
    )
    (net (code "31") (name "unconnected-(U1I-NC-PadY12)") (class "Default")
      (node (ref "U1") (pin "Y12") (pinfunction "NC_Y12") (pintype "passive+no_connect"))
    )
    (net (code "32") (name "unconnected-(U1I-NC-PadY13)") (class "Default")
      (node (ref "U1") (pin "Y13") (pinfunction "NC_Y13") (pintype "passive+no_connect"))
    )
  )
)
